# 1-Schematic_LoPoSwitchWiFI.net
KiCad netlist of a schematic drawn in EasyEDA
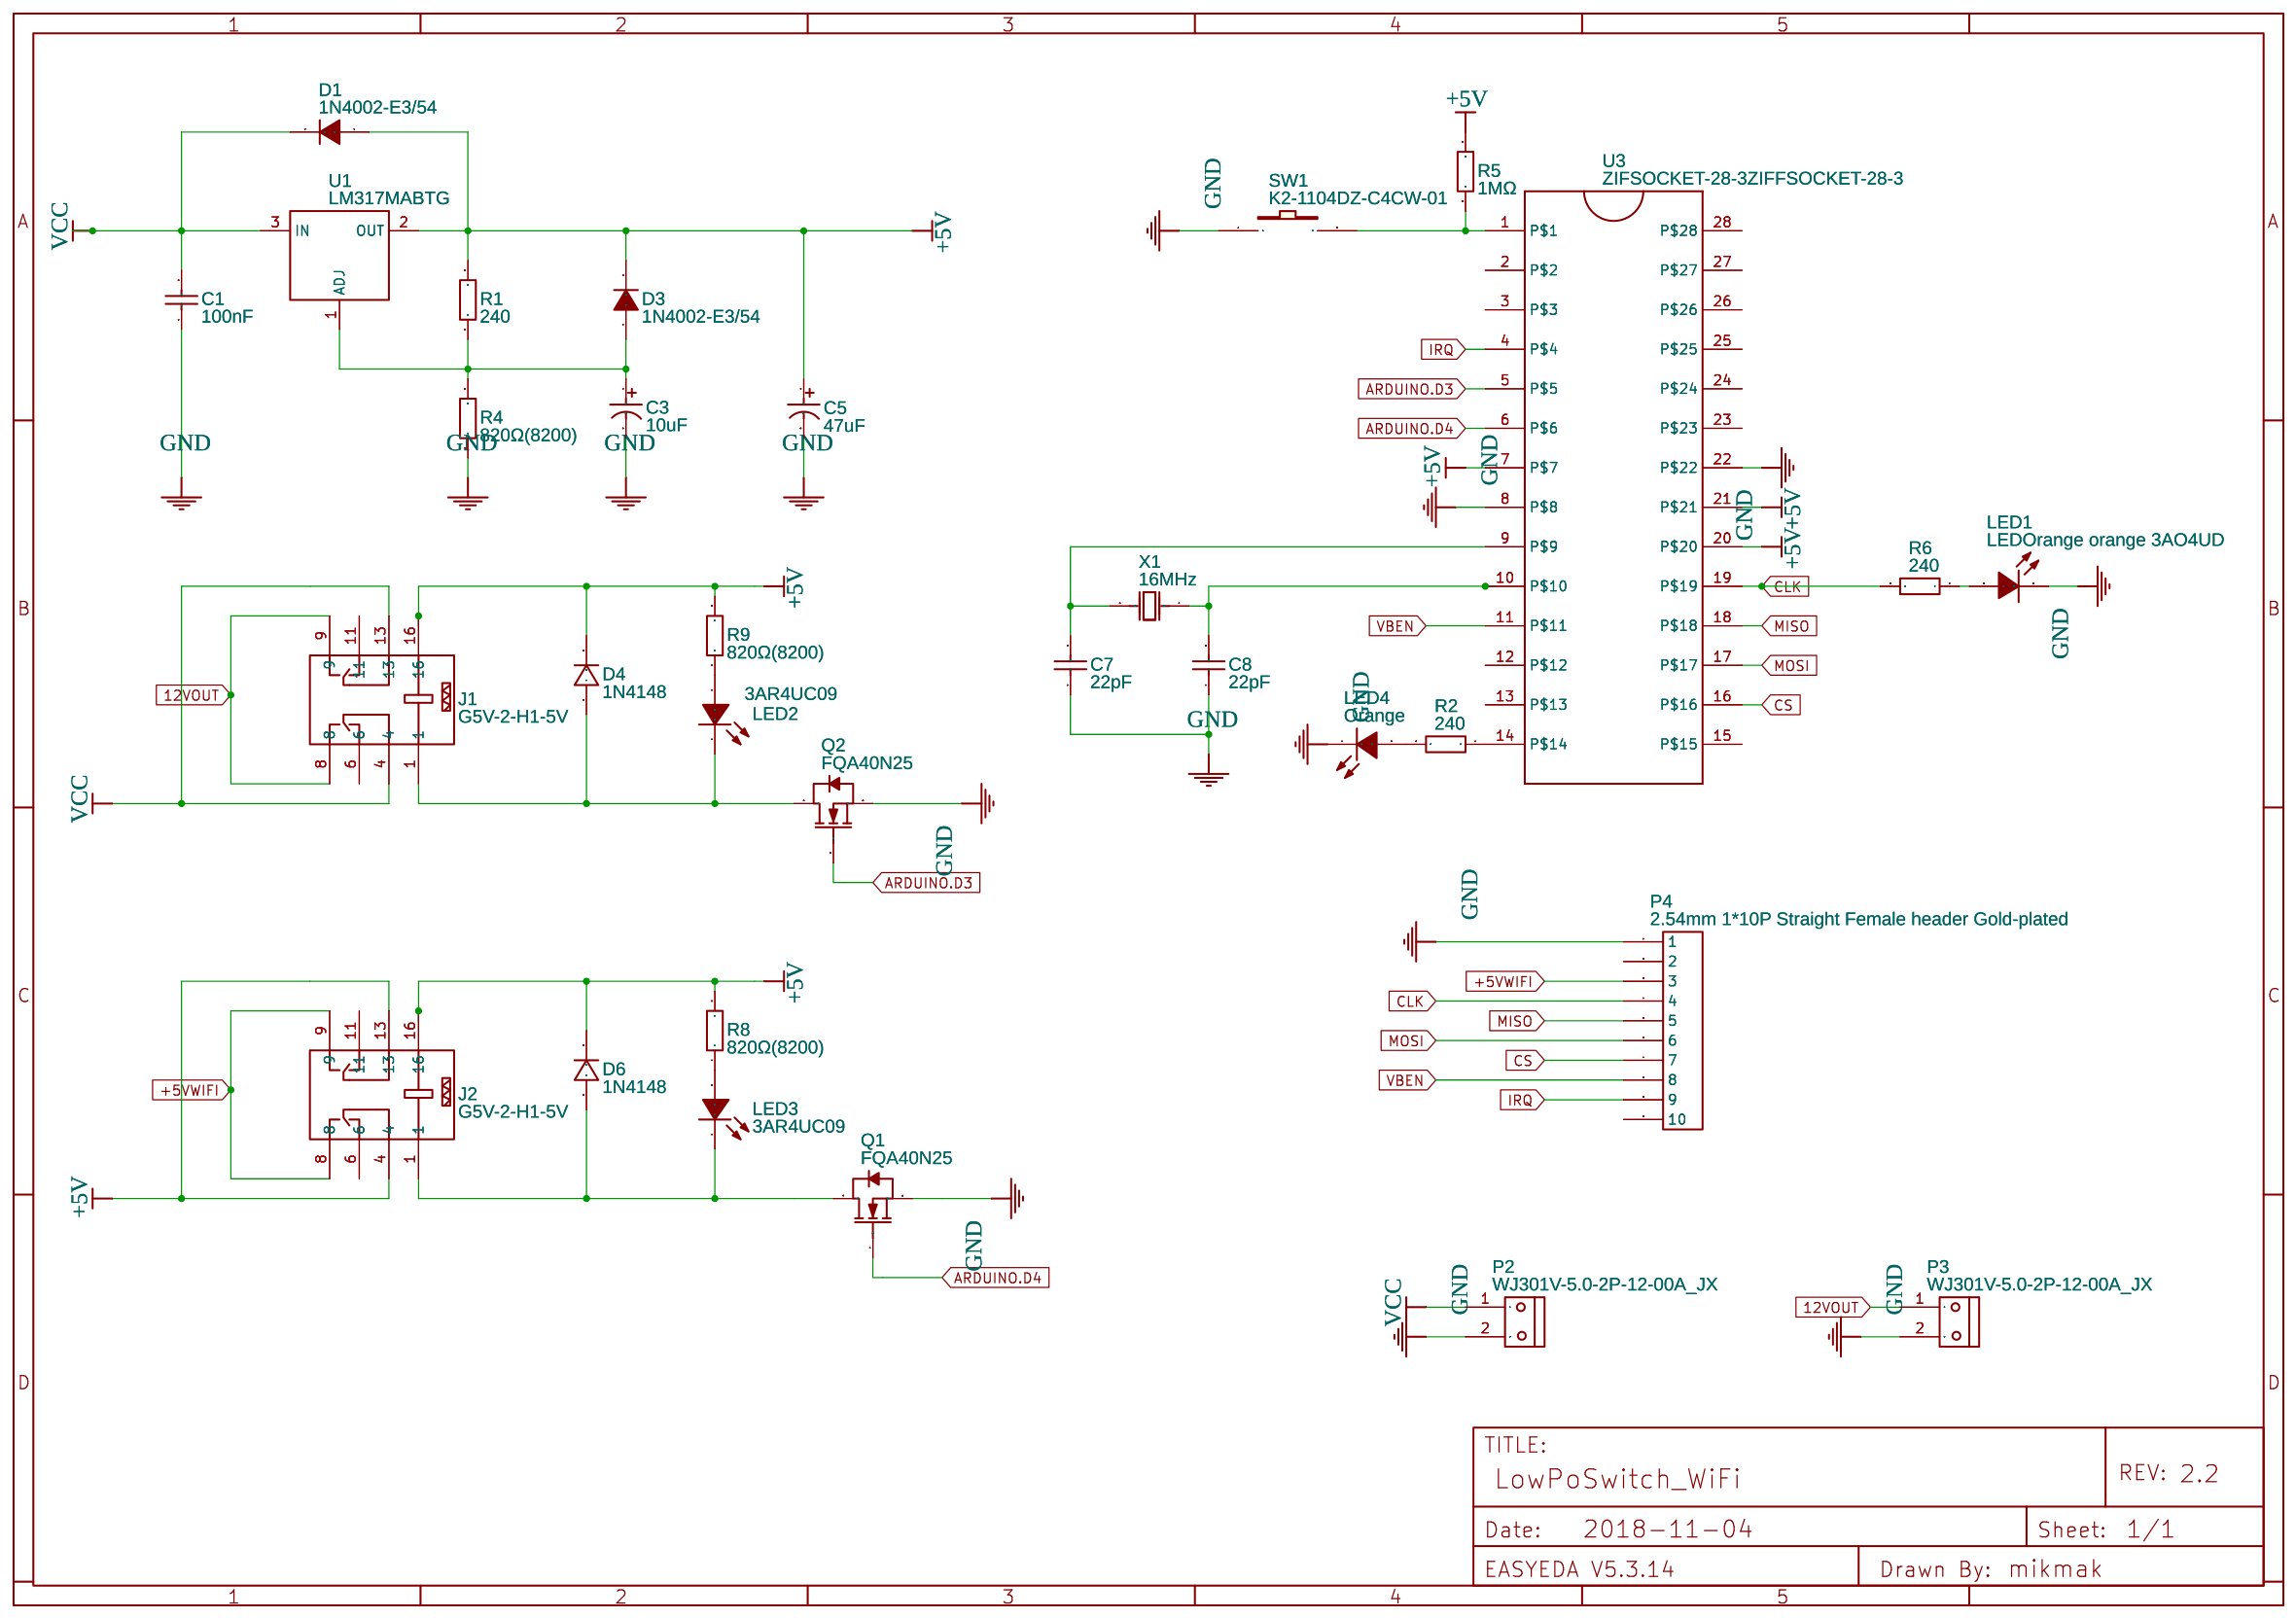
[diagram p0: schematic sheet]

(export (version "E")
  (design (tool "Eeschema 10.0.6"))
  (components
    (comp (ref "C1")
      (value "100nF")
      (fields
        (field (name "BOM_Manufacturer Part") "MPP104K5130508LC")
        (field (name "BOM_Supplier Part") "C109523")
      )
      (libsource (lib "") (part "MPP104K5130508LC"))
    )
    (comp (ref "C3")
      (value "10uF")
      (fields (field (name "BOM_Manufacturer Part") "10uf/100V") (field (name "BOM_Supplier Part") "C2029"))
      (libsource (lib "") (part "10uf/100V"))
    )
    (comp (ref "C5")
      (value "47uF")
      (fields (field (name "BOM_Manufacturer Part") "47UF16V") (field (name "BOM_Supplier Part") "C30224"))
      (libsource (lib "") (part "47UF16V"))
    )
    (comp (ref "C7")
      (value "22pF")
      (fields
        (field (name "BOM_Manufacturer Part") "Monolithic0603N220J500")
        (field (name "BOM_Supplier Part") "C110283")
      )
      (libsource (lib "") (part "Monolithic0603N220J500"))
    )
    (comp (ref "C8")
      (value "22pF")
      (fields
        (field (name "BOM_Manufacturer Part") "Monolithic0603N220J500")
        (field (name "BOM_Supplier Part") "C110283")
      )
      (libsource (lib "") (part "Monolithic0603N220J500"))
    )
    (comp (ref "D1")
      (value "1N4002-E3/54")
      (fields (field (name "BOM_Supplier Part") "C33504"))
      (libsource (lib "") (part "Unknown_160_60"))
    )
    (comp (ref "D3")
      (value "1N4002-E3/54")
      (fields (field (name "BOM_Supplier Part") "C33504"))
      (libsource (lib "") (part "Unknown_310_145"))
    )
    (comp (ref "D4")
      (value "1N4148")
      (fields (field (name "BOM_Supplier Part") "C163750"))
      (libsource (lib "") (part "Unknown_290_335"))
    )
    (comp (ref "D6")
      (value "1N4148")
      (fields (field (name "BOM_Supplier Part") "C163750"))
      (libsource (lib "") (part "Unknown_290_535"))
    )
    (comp (ref "J1")
      (value "G5V-2-H1-5V")
      (fields (field (name "BOM_Supplier Part") "C28066"))
      (libsource (lib "") (part "Unknown_185_340"))
    )
    (comp (ref "J2")
      (value "G5V-2-H1-5V")
      (fields (field (name "BOM_Supplier Part") "C28066"))
      (libsource (lib "") (part "Unknown_185_540"))
    )
    (comp (ref "LED1")
      (value "LEDOrange orange 3AO4UD")
      (fields (field (name "BOM_Supplier Part") "C62095"))
      (libsource (lib "") (part "Unknown_1010_290"))
    )
    (comp (ref "LED2")
      (value "3AR4UC09")
      (fields (field (name "BOM_Supplier Part") "C6211"))
      (libsource (lib "") (part "Unknown_355_355"))
    )
    (comp (ref "LED3")
      (value "3AR4UC09")
      (fields (field (name "BOM_Supplier Part") "C6211"))
      (libsource (lib "") (part "Unknown_355_555"))
    )
    (comp (ref "LED4")
      (value "Orange")
      (fields
        (field (name "BOM_Manufacturer Part") "LEDOrange orange 3AO4UD")
        (field (name "BOM_Supplier Part") "C62095")
      )
      (libsource (lib "") (part "Unknown_685_370"))
    )
    (comp (ref "P2")
      (value "WJ301V-5.0-2P-12-00A_JX")
      (fields (field (name "BOM_Manufacturer Part") "?") (field (name "BOM_Supplier Part") "C72326"))
      (libsource (lib "") (part "Unknown_755_655"))
    )
    (comp (ref "P3")
      (value "WJ301V-5.0-2P-12-00A_JX")
      (fields (field (name "BOM_Manufacturer Part") "?") (field (name "BOM_Supplier Part") "C72326"))
      (libsource (lib "") (part "Unknown_975_655"))
    )
    (comp (ref "P4")
      (value "2.54mm 1*10P Straight Female header Gold-plated")
      (fields (field (name "BOM_Supplier Part") "C35445"))
      (libsource (lib "") (part "Unknown_825_510"))
    )
    (comp (ref "Q1")
      (value "FQA40N25")
      (fields (field (name "BOM_Supplier Part") "C10877"))
      (libsource (lib "") (part "Unknown_435_610"))
    )
    (comp (ref "Q2")
      (value "FQA40N25")
      (fields (field (name "BOM_Supplier Part") "C10877"))
      (libsource (lib "") (part "Unknown_415_410"))
    )
    (comp (ref "R1")
      (value "240")
      (fields
        (field (name "BOM_Manufacturer Part") "MF1/8W-240Ω±1% T52")
        (field (name "BOM_Supplier Part") "C119165")
      )
      (libsource (lib "") (part "MF1/8W-240Ω±1% T52"))
    )
    (comp (ref "R2")
      (value "240")
      (fields
        (field (name "BOM_Manufacturer Part") "MF1/8W-240Ω±1% T52")
        (field (name "BOM_Supplier Part") "C119165")
      )
      (libsource (lib "") (part "MF1/8W-240Ω±1% T52_1"))
    )
    (comp (ref "R4")
      (value "820Ω(8200)")
      (fields
        (field (name "BOM_Manufacturer Part") "MF1/8W-820Ω±1% T52")
        (field (name "BOM_Supplier Part") "C119177")
      )
      (libsource (lib "") (part "MF1/8W-820Ω±1% T52"))
    )
    (comp (ref "R5")
      (value "1MΩ")
      (fields
        (field (name "BOM_Manufacturer Part") "MFR0W4F1004A50")
        (field (name "BOM_Supplier Part") "C58596")
      )
      (libsource (lib "") (part "MFR0W4F1004A50"))
    )
    (comp (ref "R6")
      (value "240")
      (fields
        (field (name "BOM_Manufacturer Part") "MF1/8W-240Ω±1% T52")
        (field (name "BOM_Supplier Part") "C119165")
      )
      (libsource (lib "") (part "MF1/8W-240Ω±1% T52_1"))
    )
    (comp (ref "R8")
      (value "820Ω(8200)")
      (fields
        (field (name "BOM_Manufacturer Part") "MF1/8W-820Ω±1% T52")
        (field (name "BOM_Supplier Part") "C119177")
      )
      (libsource (lib "") (part "MF1/8W-820Ω±1% T52"))
    )
    (comp (ref "R9")
      (value "820Ω(8200)")
      (fields
        (field (name "BOM_Manufacturer Part") "MF1/8W-820Ω±1% T52")
        (field (name "BOM_Supplier Part") "C119177")
      )
      (libsource (lib "") (part "MF1/8W-820Ω±1% T52"))
    )
    (comp (ref "SW1")
      (value "K2-1104DZ-C4CW-01")
      (fields (field (name "BOM_Supplier Part") "C145889"))
      (libsource (lib "") (part "Unknown_640_110"))
    )
    (comp (ref "U1")
      (value "LM317MABTG")
      (fields (field (name "BOM_Supplier Part") "C94823"))
      (libsource (lib "") (part "Unknown_165_120"))
    )
    (comp (ref "U3")
      (value "ZIFSOCKET-28-3ZIFFSOCKET-28-3")
      (fields (field (name "BOM_Manufacturer Part") "?"))
      (libsource (lib "") (part "Unknown_765_390"))
    )
    (comp (ref "X1")
      (value "16MHz")
      (fields
        (field (name "BOM_Manufacturer Part") "X49SD16MSD2SC")
        (field (name "BOM_Supplier Part") "C16212")
      )
      (libsource (lib "") (part "X49SD16MSD2SC"))
    )
  )
  (nets
    (net (code "1") (name "+5V") (class "Default")
      (node (ref "C5") (pin "1") (pinfunction "1_1") (pintype "input"))
      (node (ref "D1") (pin "1") (pinfunction "A_1") (pintype "unspecified"))
      (node (ref "D3") (pin "2") (pinfunction "K_2") (pintype "unspecified"))
      (node (ref "D4") (pin "2") (pinfunction "2_2") (pintype "unspecified"))
      (node (ref "D6") (pin "2") (pinfunction "2_2") (pintype "unspecified"))
      (node (ref "J1") (pin "16") (pinfunction "16_16") (pintype "unspecified"))
      (node (ref "J2") (pin "13") (pinfunction "13_13") (pintype "unspecified"))
      (node (ref "J2") (pin "16") (pinfunction "16_16") (pintype "unspecified"))
      (node (ref "J2") (pin "4") (pinfunction "4_4") (pintype "unspecified"))
      (node (ref "R1") (pin "2") (pinfunction "2_2") (pintype "input"))
      (node (ref "R5") (pin "2") (pinfunction "2_2") (pintype "input"))
      (node (ref "R8") (pin "2") (pinfunction "2_2") (pintype "input"))
      (node (ref "R9") (pin "2") (pinfunction "2_2") (pintype "input"))
      (node (ref "U1") (pin "2") (pinfunction "OUT_2") (pintype "unspecified"))
      (node (ref "U3") (pin "20") (pinfunction "P$20_20") (pintype "unspecified"))
      (node (ref "U3") (pin "21") (pinfunction "P$21_21") (pintype "unspecified"))
      (node (ref "U3") (pin "7") (pinfunction "P$7_7") (pintype "unspecified"))
    )
    (net (code "2") (name "+5VWIFI") (class "Default")
      (node (ref "J2") (pin "8") (pinfunction "8_8") (pintype "unspecified"))
      (node (ref "J2") (pin "9") (pinfunction "9_9") (pintype "unspecified"))
      (node (ref "P4") (pin "3") (pinfunction "3_3") (pintype "input"))
    )
    (net (code "3") (name "12VOUT") (class "Default")
      (node (ref "J1") (pin "8") (pinfunction "8_8") (pintype "unspecified"))
      (node (ref "J1") (pin "9") (pinfunction "9_9") (pintype "unspecified"))
      (node (ref "P3") (pin "1") (pinfunction "1_1") (pintype "unspecified"))
    )
    (net (code "4") (name "ARDUINO.D3") (class "Default")
      (node (ref "Q2") (pin "1") (pinfunction "G_1") (pintype "unspecified"))
      (node (ref "U3") (pin "5") (pinfunction "P$5_5") (pintype "unspecified"))
    )
    (net (code "5") (name "ARDUINO.D4") (class "Default")
      (node (ref "Q1") (pin "1") (pinfunction "G_1") (pintype "unspecified"))
      (node (ref "U3") (pin "6") (pinfunction "P$6_6") (pintype "unspecified"))
    )
    (net (code "6") (name "CLK") (class "Default")
      (node (ref "P4") (pin "4") (pinfunction "4_4") (pintype "input"))
      (node (ref "R6") (pin "2") (pinfunction "2_2") (pintype "input"))
      (node (ref "U3") (pin "19") (pinfunction "P$19_19") (pintype "unspecified"))
    )
    (net (code "7") (name "CS") (class "Default")
      (node (ref "P4") (pin "7") (pinfunction "7_7") (pintype "input"))
      (node (ref "U3") (pin "16") (pinfunction "P$16_16") (pintype "unspecified"))
    )
    (net (code "8") (name "GND") (class "Default")
      (node (ref "C1") (pin "1") (pinfunction "1_1") (pintype "input"))
      (node (ref "C3") (pin "2") (pinfunction "2_2") (pintype "input"))
      (node (ref "C5") (pin "2") (pinfunction "2_2") (pintype "input"))
      (node (ref "C7") (pin "1") (pinfunction "1_1") (pintype "input"))
      (node (ref "C8") (pin "1") (pinfunction "1_1") (pintype "input"))
      (node (ref "LED1") (pin "1") (pinfunction "K_1") (pintype "unspecified"))
      (node (ref "LED4") (pin "1") (pinfunction "K_1") (pintype "unspecified"))
      (node (ref "P2") (pin "2") (pinfunction "2_2") (pintype "unspecified"))
      (node (ref "P3") (pin "2") (pinfunction "2_2") (pintype "unspecified"))
      (node (ref "P4") (pin "1") (pinfunction "1_1") (pintype "input"))
      (node (ref "Q1") (pin "3") (pinfunction "S_3") (pintype "unspecified"))
      (node (ref "Q2") (pin "3") (pinfunction "S_3") (pintype "unspecified"))
      (node (ref "R4") (pin "1") (pinfunction "1_1") (pintype "input"))
      (node (ref "SW1") (pin "1") (pinfunction "1_1") (pintype "input"))
      (node (ref "U3") (pin "22") (pinfunction "P$22_22") (pintype "unspecified"))
      (node (ref "U3") (pin "8") (pinfunction "P$8_8") (pintype "unspecified"))
    )
    (net (code "9") (name "IRQ") (class "Default")
      (node (ref "P4") (pin "9") (pinfunction "9_9") (pintype "input"))
      (node (ref "U3") (pin "4") (pinfunction "P$4_4") (pintype "unspecified"))
    )
    (net (code "10") (name "MISO") (class "Default")
      (node (ref "P4") (pin "5") (pinfunction "5_5") (pintype "input"))
      (node (ref "U3") (pin "18") (pinfunction "P$18_18") (pintype "unspecified"))
    )
    (net (code "11") (name "MOSI") (class "Default")
      (node (ref "P4") (pin "6") (pinfunction "6_6") (pintype "input"))
      (node (ref "U3") (pin "17") (pinfunction "P$17_17") (pintype "unspecified"))
    )
    (net (code "12") (name "Net-(D3-A)") (class "Default")
      (node (ref "C3") (pin "1") (pinfunction "1_1") (pintype "input"))
      (node (ref "D3") (pin "1") (pinfunction "A_1") (pintype "unspecified"))
      (node (ref "R1") (pin "1") (pinfunction "1_1") (pintype "input"))
      (node (ref "R4") (pin "2") (pinfunction "2_2") (pintype "input"))
      (node (ref "U1") (pin "1") (pinfunction "ADJ_1") (pintype "input"))
    )
    (net (code "13") (name "Net-(LED1-A)") (class "Default")
      (node (ref "LED1") (pin "2") (pinfunction "A_2") (pintype "unspecified"))
      (node (ref "R6") (pin "1") (pinfunction "1_1") (pintype "input"))
    )
    (net (code "14") (name "Net-(LED2-A)") (class "Default")
      (node (ref "LED2") (pin "2") (pinfunction "A_2") (pintype "unspecified"))
      (node (ref "R9") (pin "1") (pinfunction "1_1") (pintype "input"))
    )
    (net (code "15") (name "Net-(LED2-K)") (class "Default")
      (node (ref "D4") (pin "1") (pinfunction "1_1") (pintype "unspecified"))
      (node (ref "J1") (pin "1") (pinfunction "1_1") (pintype "unspecified"))
      (node (ref "LED2") (pin "1") (pinfunction "K_1") (pintype "unspecified"))
      (node (ref "Q2") (pin "2") (pinfunction "D_2") (pintype "unspecified"))
    )
    (net (code "16") (name "Net-(LED3-A)") (class "Default")
      (node (ref "LED3") (pin "2") (pinfunction "A_2") (pintype "unspecified"))
      (node (ref "R8") (pin "1") (pinfunction "1_1") (pintype "input"))
    )
    (net (code "17") (name "Net-(LED3-K)") (class "Default")
      (node (ref "D6") (pin "1") (pinfunction "1_1") (pintype "unspecified"))
      (node (ref "J2") (pin "1") (pinfunction "1_1") (pintype "unspecified"))
      (node (ref "LED3") (pin "1") (pinfunction "K_1") (pintype "unspecified"))
      (node (ref "Q1") (pin "2") (pinfunction "D_2") (pintype "unspecified"))
    )
    (net (code "18") (name "Net-(LED4-A)") (class "Default")
      (node (ref "LED4") (pin "2") (pinfunction "A_2") (pintype "unspecified"))
      (node (ref "R2") (pin "2") (pinfunction "2_2") (pintype "input"))
    )
    (net (code "19") (name "Net-(U3-P$1)") (class "Default")
      (node (ref "R5") (pin "1") (pinfunction "1_1") (pintype "input"))
      (node (ref "SW1") (pin "2") (pinfunction "2_2") (pintype "input"))
      (node (ref "U3") (pin "1") (pinfunction "P$1_1") (pintype "unspecified"))
    )
    (net (code "20") (name "Net-(U3-P$9)") (class "Default")
      (node (ref "C7") (pin "2") (pinfunction "2_2") (pintype "input"))
      (node (ref "U3") (pin "9") (pinfunction "P$9_9") (pintype "unspecified"))
      (node (ref "X1") (pin "2") (pinfunction "OSC2_2") (pintype "input"))
    )
    (net (code "21") (name "Net-(U3-P$10)") (class "Default")
      (node (ref "C8") (pin "2") (pinfunction "2_2") (pintype "input"))
      (node (ref "U3") (pin "10") (pinfunction "P$10_10") (pintype "unspecified"))
      (node (ref "X1") (pin "1") (pinfunction "OSC1_1") (pintype "input"))
    )
    (net (code "22") (name "Net-(U3-P$14)") (class "Default")
      (node (ref "R2") (pin "1") (pinfunction "1_1") (pintype "input"))
      (node (ref "U3") (pin "14") (pinfunction "P$14_14") (pintype "unspecified"))
    )
    (net (code "23") (name "VBEN") (class "Default")
      (node (ref "P4") (pin "8") (pinfunction "8_8") (pintype "input"))
      (node (ref "U3") (pin "11") (pinfunction "P$11_11") (pintype "unspecified"))
    )
    (net (code "24") (name "VCC") (class "Default")
      (node (ref "C1") (pin "2") (pinfunction "2_2") (pintype "input"))
      (node (ref "D1") (pin "2") (pinfunction "K_2") (pintype "unspecified"))
      (node (ref "J1") (pin "13") (pinfunction "13_13") (pintype "unspecified"))
      (node (ref "J1") (pin "4") (pinfunction "4_4") (pintype "unspecified"))
      (node (ref "P2") (pin "1") (pinfunction "1_1") (pintype "unspecified"))
      (node (ref "U1") (pin "3") (pinfunction "IN_3") (pintype "input"))
    )
    (net (code "25") (name "unconnected-(J1-Pad6)") (class "Default")
      (node (ref "J1") (pin "6") (pinfunction "6_6") (pintype "unspecified"))
    )
    (net (code "26") (name "unconnected-(J1-Pad11)") (class "Default")
      (node (ref "J1") (pin "11") (pinfunction "11_11") (pintype "unspecified"))
    )
    (net (code "27") (name "unconnected-(J2-Pad6)") (class "Default")
      (node (ref "J2") (pin "6") (pinfunction "6_6") (pintype "unspecified"))
    )
    (net (code "28") (name "unconnected-(J2-Pad11)") (class "Default")
      (node (ref "J2") (pin "11") (pinfunction "11_11") (pintype "unspecified"))
    )
    (net (code "29") (name "unconnected-(P4-Pad2)") (class "Default")
      (node (ref "P4") (pin "2") (pinfunction "2_2") (pintype "input"))
    )
    (net (code "30") (name "unconnected-(P4-Pad10)") (class "Default")
      (node (ref "P4") (pin "10") (pinfunction "10_10") (pintype "input"))
    )
    (net (code "31") (name "unconnected-(U3-P$2-Pad2)") (class "Default")
      (node (ref "U3") (pin "2") (pinfunction "P$2_2") (pintype "unspecified"))
    )
    (net (code "32") (name "unconnected-(U3-P$3-Pad3)") (class "Default")
      (node (ref "U3") (pin "3") (pinfunction "P$3_3") (pintype "unspecified"))
    )
    (net (code "33") (name "unconnected-(U3-P$12-Pad12)") (class "Default")
      (node (ref "U3") (pin "12") (pinfunction "P$12_12") (pintype "unspecified"))
    )
    (net (code "34") (name "unconnected-(U3-P$13-Pad13)") (class "Default")
      (node (ref "U3") (pin "13") (pinfunction "P$13_13") (pintype "unspecified"))
    )
    (net (code "35") (name "unconnected-(U3-P$15-Pad15)") (class "Default")
      (node (ref "U3") (pin "15") (pinfunction "P$15_15") (pintype "unspecified"))
    )
    (net (code "36") (name "unconnected-(U3-P$23-Pad23)") (class "Default")
      (node (ref "U3") (pin "23") (pinfunction "P$23_23") (pintype "unspecified"))
    )
    (net (code "37") (name "unconnected-(U3-P$24-Pad24)") (class "Default")
      (node (ref "U3") (pin "24") (pinfunction "P$24_24") (pintype "unspecified"))
    )
    (net (code "38") (name "unconnected-(U3-P$25-Pad25)") (class "Default")
      (node (ref "U3") (pin "25") (pinfunction "P$25_25") (pintype "unspecified"))
    )
    (net (code "39") (name "unconnected-(U3-P$26-Pad26)") (class "Default")
      (node (ref "U3") (pin "26") (pinfunction "P$26_26") (pintype "unspecified"))
    )
    (net (code "40") (name "unconnected-(U3-P$27-Pad27)") (class "Default")
      (node (ref "U3") (pin "27") (pinfunction "P$27_27") (pintype "unspecified"))
    )
    (net (code "41") (name "unconnected-(U3-P$28-Pad28)") (class "Default")
      (node (ref "U3") (pin "28") (pinfunction "P$28_28") (pintype "unspecified"))
    )
  )
)
